# rv_pwr_es_ctrl.net
KiCad netlist of a schematic drawn in Altium Designer
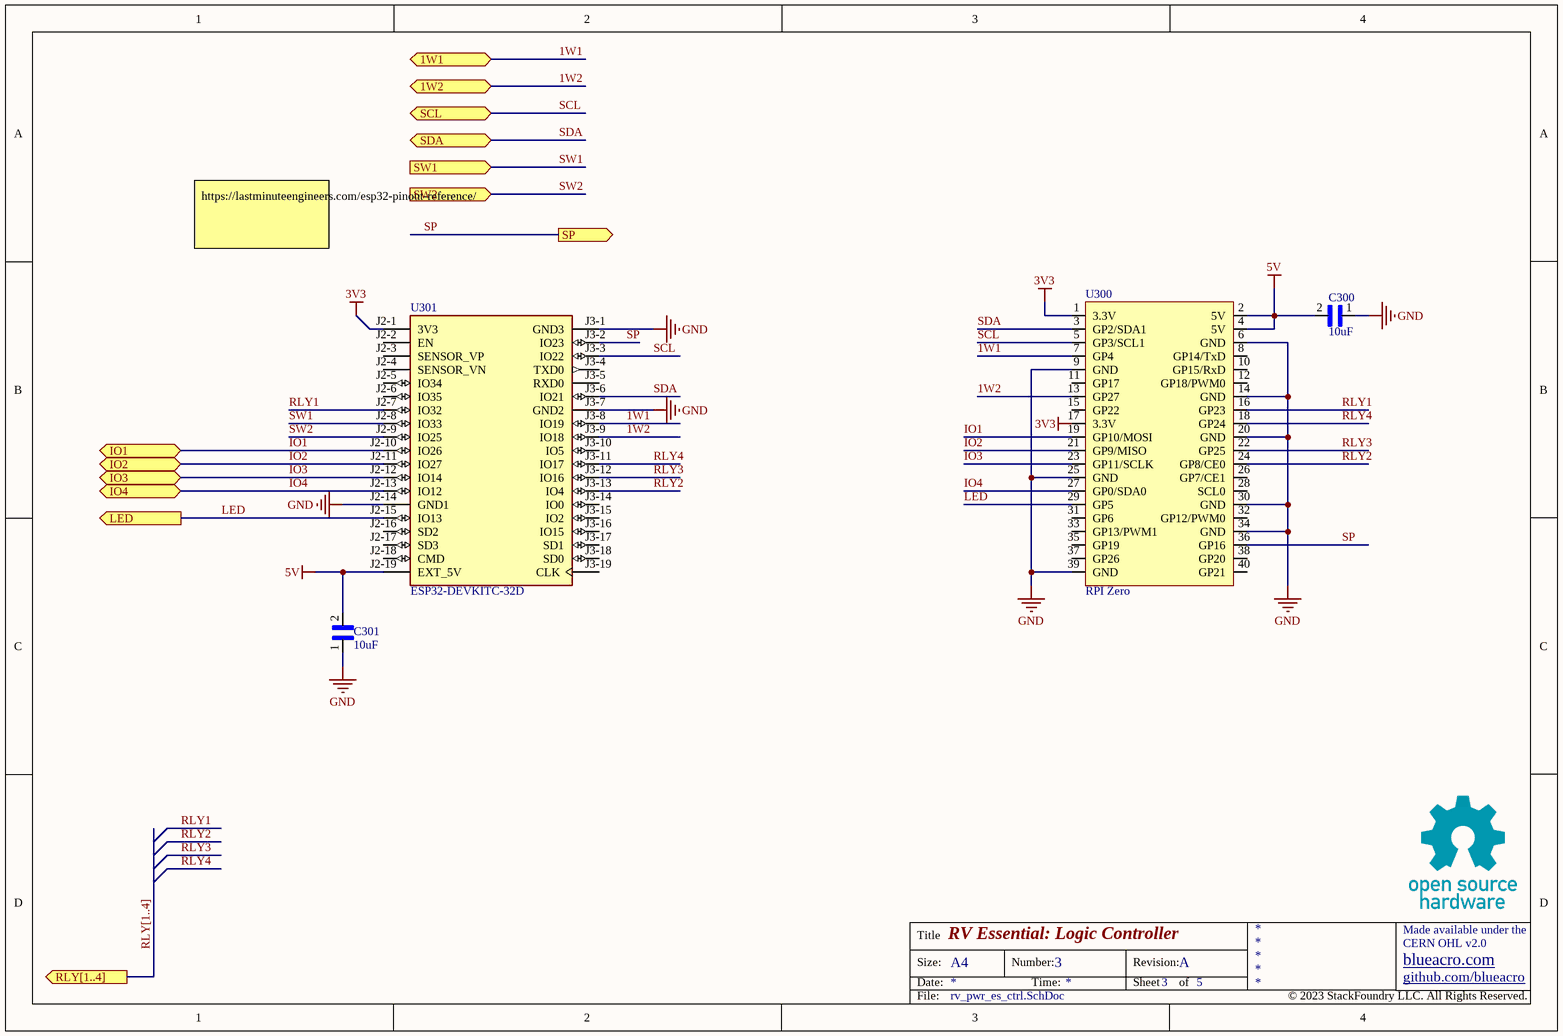
[diagram p0: rv_pwr_es_ctrl.SchDoc]

(export (version "E")
  (design (tool "Eeschema 10.0.6"))
  (components
    (comp (ref "C300")
      (value "10uF")
      (footprint "CAPRB250W50L550T350H600")
      (description "FG Series 10 uF 25 V ±10% Tolerance X7R Radial Multilayer Ceramic Capacitor")
      (fields (field (name "MF") "TDK") (field (name "DIGI-KEY_PART_NUMBER") "445-173156-1-ND"))
      (libsource (lib "") (part "FG16X7R1E106KRT06_1"))
    )
    (comp (ref "C301")
      (value "10uF")
      (footprint "CAPRB250W50L550T350H600")
      (description "FG Series 10 uF 25 V ±10% Tolerance X7R Radial Multilayer Ceramic Capacitor")
      (fields (field (name "MF") "TDK") (field (name "DIGI-KEY_PART_NUMBER") "445-173156-1-ND"))
      (libsource (lib "StackFoundry LLC") (part "FG16X7R1E106KRT06"))
    )
    (comp (ref "U300")
      (value "RPI Zero")
      (footprint "RPI_ZERO_W")
      (libsource (lib "StackFoundry LLC") (part "RPI Zero"))
    )
    (comp (ref "U301")
      (value "ESP32-DEVKITC-32D")
      (footprint "MODULE_ESP32-DEVKITC-32D")
      (description "WiFi Development Tools (802.11) ESP32 General Development Kit, ESP32-WROOM-32D on the board")
      (fields (field (name "MF") "Espressif Systems"))
      (libsource (lib "StackFoundry LLC") (part "ESP32-DEVKITC-32D"))
    )
  )
  (nets
    (net (code "1") (name "/1W1") (class "Default")
      (node (ref "U300") (pin "7") (pinfunction "GP4_7") (pintype "passive"))
      (node (ref "U301") (pin "J3-8") (pinfunction "IO19_J3-8") (pintype "bidirectional"))
    )
    (net (code "2") (name "/1W2") (class "Default")
      (node (ref "U300") (pin "13") (pinfunction "GP27_13") (pintype "passive"))
      (node (ref "U301") (pin "J3-9") (pinfunction "IO18_J3-9") (pintype "bidirectional"))
    )
    (net (code "3") (name "/IO1") (class "Default")
      (node (ref "U300") (pin "19") (pinfunction "GP10/MOSI_19") (pintype "passive"))
      (node (ref "U301") (pin "J2-10") (pinfunction "IO26_J2-10") (pintype "bidirectional"))
    )
    (net (code "4") (name "/IO2") (class "Default")
      (node (ref "U300") (pin "21") (pinfunction "GP9/MISO_21") (pintype "passive"))
      (node (ref "U301") (pin "J2-11") (pinfunction "IO27_J2-11") (pintype "bidirectional"))
    )
    (net (code "5") (name "/IO3") (class "Default")
      (node (ref "U300") (pin "23") (pinfunction "GP11/SCLK_23") (pintype "passive"))
      (node (ref "U301") (pin "J2-12") (pinfunction "IO14_J2-12") (pintype "bidirectional"))
    )
    (net (code "6") (name "/IO4") (class "Default")
      (node (ref "U300") (pin "27") (pinfunction "GP0/SDA0_27") (pintype "passive"))
      (node (ref "U301") (pin "J2-13") (pinfunction "IO12_J2-13") (pintype "bidirectional"))
    )
    (net (code "7") (name "/LED") (class "Default")
      (node (ref "U300") (pin "29") (pinfunction "GP5_29") (pintype "passive"))
      (node (ref "U301") (pin "J2-15") (pinfunction "IO13_J2-15") (pintype "bidirectional"))
    )
    (net (code "8") (name "/RLY1") (class "Default")
      (node (ref "U300") (pin "16") (pinfunction "GP23_16") (pintype "passive"))
      (node (ref "U301") (pin "J2-7") (pinfunction "IO32_J2-7") (pintype "bidirectional"))
    )
    (net (code "9") (name "/RLY2") (class "Default")
      (node (ref "U300") (pin "24") (pinfunction "GP8/CE0_24") (pintype "passive"))
      (node (ref "U301") (pin "J3-13") (pinfunction "IO4_J3-13") (pintype "bidirectional"))
    )
    (net (code "10") (name "/RLY3") (class "Default")
      (node (ref "U300") (pin "22") (pinfunction "GP25_22") (pintype "passive"))
      (node (ref "U301") (pin "J3-12") (pinfunction "IO16_J3-12") (pintype "bidirectional"))
    )
    (net (code "11") (name "/RLY4") (class "Default")
      (node (ref "U300") (pin "18") (pinfunction "GP24_18") (pintype "passive"))
      (node (ref "U301") (pin "J3-11") (pinfunction "IO17_J3-11") (pintype "bidirectional"))
    )
    (net (code "13") (name "/SCL") (class "Default")
      (node (ref "U300") (pin "5") (pinfunction "GP3/SCL1_5") (pintype "passive"))
      (node (ref "U301") (pin "J3-3") (pinfunction "IO22_J3-3") (pintype "bidirectional"))
    )
    (net (code "14") (name "/SDA") (class "Default")
      (node (ref "U300") (pin "3") (pinfunction "GP2/SDA1_3") (pintype "passive"))
      (node (ref "U301") (pin "J3-6") (pinfunction "IO21_J3-6") (pintype "bidirectional"))
    )
    (net (code "15") (name "/SP") (class "Default")
      (node (ref "U300") (pin "36") (pinfunction "GP16_36") (pintype "passive"))
      (node (ref "U301") (pin "J3-2") (pinfunction "IO23_J3-2") (pintype "bidirectional"))
    )
    (net (code "16") (name "/SW1") (class "Default")
      (node (ref "U301") (pin "J2-8") (pinfunction "IO33_J2-8") (pintype "bidirectional"))
    )
    (net (code "17") (name "/SW2") (class "Default")
      (node (ref "U301") (pin "J2-9") (pinfunction "IO25_J2-9") (pintype "bidirectional"))
    )
    (net (code "18") (name "3V3") (class "Default")
      (node (ref "U300") (pin "1") (pinfunction "3.3V_1") (pintype "passive"))
      (node (ref "U300") (pin "17") (pinfunction "3.3V_17") (pintype "passive"))
      (node (ref "U301") (pin "J2-1") (pinfunction "3V3_J2-1") (pintype "power_in"))
    )
    (net (code "19") (name "5V") (class "Default")
      (node (ref "C300") (pin "2") (pinfunction "2_2") (pintype "passive"))
      (node (ref "C301") (pin "2") (pinfunction "2_2") (pintype "passive"))
      (node (ref "U300") (pin "2") (pinfunction "5V_2") (pintype "passive"))
      (node (ref "U300") (pin "4") (pinfunction "5V_4") (pintype "passive"))
      (node (ref "U301") (pin "J2-19") (pinfunction "EXT_5V_J2-19") (pintype "power_in"))
    )
    (net (code "20") (name "GND") (class "Default")
      (node (ref "C300") (pin "1") (pinfunction "1_1") (pintype "passive"))
      (node (ref "C301") (pin "1") (pinfunction "1_1") (pintype "passive"))
      (node (ref "U300") (pin "14") (pinfunction "GND_14") (pintype "passive"))
      (node (ref "U300") (pin "20") (pinfunction "GND_20") (pintype "passive"))
      (node (ref "U300") (pin "25") (pinfunction "GND_25") (pintype "passive"))
      (node (ref "U300") (pin "30") (pinfunction "GND_30") (pintype "passive"))
      (node (ref "U300") (pin "34") (pinfunction "GND_34") (pintype "passive"))
      (node (ref "U300") (pin "39") (pinfunction "GND_39") (pintype "passive"))
      (node (ref "U300") (pin "6") (pinfunction "GND_6") (pintype "passive"))
      (node (ref "U300") (pin "9") (pinfunction "GND_9") (pintype "passive"))
      (node (ref "U301") (pin "J2-14") (pinfunction "GND1_J2-14") (pintype "power_in"))
      (node (ref "U301") (pin "J3-1") (pinfunction "GND3_J3-1") (pintype "power_in"))
      (node (ref "U301") (pin "J3-7") (pinfunction "GND2_J3-7") (pintype "power_in"))
    )
    (net (code "21") (name "unconnected-(U300-GP6-Pad31)") (class "Default")
      (node (ref "U300") (pin "31") (pinfunction "GP6_31") (pintype "passive"))
    )
    (net (code "22") (name "unconnected-(U300-GP7{slash}CE1-Pad26)") (class "Default")
      (node (ref "U300") (pin "26") (pinfunction "GP7/CE1_26") (pintype "passive"))
    )
    (net (code "23") (name "unconnected-(U300-GP12{slash}PWM0-Pad32)") (class "Default")
      (node (ref "U300") (pin "32") (pinfunction "GP12/PWM0_32") (pintype "passive"))
    )
    (net (code "24") (name "unconnected-(U300-GP13{slash}PWM1-Pad33)") (class "Default")
      (node (ref "U300") (pin "33") (pinfunction "GP13/PWM1_33") (pintype "passive"))
    )
    (net (code "25") (name "unconnected-(U300-GP14{slash}TxD-Pad8)") (class "Default")
      (node (ref "U300") (pin "8") (pinfunction "GP14/TxD_8") (pintype "passive"))
    )
    (net (code "26") (name "unconnected-(U300-GP15{slash}RxD-Pad10)") (class "Default")
      (node (ref "U300") (pin "10") (pinfunction "GP15/RxD_10") (pintype "passive"))
    )
    (net (code "27") (name "unconnected-(U300-GP17-Pad11)") (class "Default")
      (node (ref "U300") (pin "11") (pinfunction "GP17_11") (pintype "passive"))
    )
    (net (code "28") (name "unconnected-(U300-GP18{slash}PWM0-Pad12)") (class "Default")
      (node (ref "U300") (pin "12") (pinfunction "GP18/PWM0_12") (pintype "passive"))
    )
    (net (code "29") (name "unconnected-(U300-GP19-Pad35)") (class "Default")
      (node (ref "U300") (pin "35") (pinfunction "GP19_35") (pintype "passive"))
    )
    (net (code "30") (name "unconnected-(U300-GP20-Pad38)") (class "Default")
      (node (ref "U300") (pin "38") (pinfunction "GP20_38") (pintype "passive"))
    )
    (net (code "31") (name "unconnected-(U300-GP21-Pad40)") (class "Default")
      (node (ref "U300") (pin "40") (pinfunction "GP21_40") (pintype "passive"))
    )
    (net (code "32") (name "unconnected-(U300-GP22-Pad15)") (class "Default")
      (node (ref "U300") (pin "15") (pinfunction "GP22_15") (pintype "passive"))
    )
    (net (code "33") (name "unconnected-(U300-GP26-Pad37)") (class "Default")
      (node (ref "U300") (pin "37") (pinfunction "GP26_37") (pintype "passive"))
    )
    (net (code "34") (name "unconnected-(U300-SCL0-Pad28)") (class "Default")
      (node (ref "U300") (pin "28") (pinfunction "SCL0_28") (pintype "passive"))
    )
    (net (code "35") (name "unconnected-(U301-CLK-PadJ3-19)") (class "Default")
      (node (ref "U301") (pin "J3-19") (pinfunction "CLK_J3-19") (pintype "passive"))
    )
    (net (code "36") (name "unconnected-(U301-CMD-PadJ2-18)") (class "Default")
      (node (ref "U301") (pin "J2-18") (pinfunction "CMD_J2-18") (pintype "bidirectional"))
    )
    (net (code "37") (name "unconnected-(U301-EN-PadJ2-2)") (class "Default")
      (node (ref "U301") (pin "J2-2") (pinfunction "EN_J2-2") (pintype "passive"))
    )
    (net (code "38") (name "unconnected-(U301-IO0-PadJ3-14)") (class "Default")
      (node (ref "U301") (pin "J3-14") (pinfunction "IO0_J3-14") (pintype "bidirectional"))
    )
    (net (code "39") (name "unconnected-(U301-IO2-PadJ3-15)") (class "Default")
      (node (ref "U301") (pin "J3-15") (pinfunction "IO2_J3-15") (pintype "bidirectional"))
    )
    (net (code "40") (name "unconnected-(U301-IO5-PadJ3-10)") (class "Default")
      (node (ref "U301") (pin "J3-10") (pinfunction "IO5_J3-10") (pintype "bidirectional"))
    )
    (net (code "41") (name "unconnected-(U301-IO15-PadJ3-16)") (class "Default")
      (node (ref "U301") (pin "J3-16") (pinfunction "IO15_J3-16") (pintype "bidirectional"))
    )
    (net (code "42") (name "unconnected-(U301-IO34-PadJ2-5)") (class "Default")
      (node (ref "U301") (pin "J2-5") (pinfunction "IO34_J2-5") (pintype "bidirectional"))
    )
    (net (code "43") (name "unconnected-(U301-IO35-PadJ2-6)") (class "Default")
      (node (ref "U301") (pin "J2-6") (pinfunction "IO35_J2-6") (pintype "bidirectional"))
    )
    (net (code "44") (name "unconnected-(U301-RXD0-PadJ3-5)") (class "Default")
      (node (ref "U301") (pin "J3-5") (pinfunction "RXD0_J3-5") (pintype "passive"))
    )
    (net (code "45") (name "unconnected-(U301-SD0-PadJ3-18)") (class "Default")
      (node (ref "U301") (pin "J3-18") (pinfunction "SD0_J3-18") (pintype "bidirectional"))
    )
    (net (code "46") (name "unconnected-(U301-SD1-PadJ3-17)") (class "Default")
      (node (ref "U301") (pin "J3-17") (pinfunction "SD1_J3-17") (pintype "bidirectional"))
    )
    (net (code "47") (name "unconnected-(U301-SD2-PadJ2-16)") (class "Default")
      (node (ref "U301") (pin "J2-16") (pinfunction "SD2_J2-16") (pintype "bidirectional"))
    )
    (net (code "48") (name "unconnected-(U301-SD3-PadJ2-17)") (class "Default")
      (node (ref "U301") (pin "J2-17") (pinfunction "SD3_J2-17") (pintype "bidirectional"))
    )
    (net (code "49") (name "unconnected-(U301-SENSOR_VN-PadJ2-4)") (class "Default")
      (node (ref "U301") (pin "J2-4") (pinfunction "SENSOR_VN_J2-4") (pintype "passive"))
    )
    (net (code "50") (name "unconnected-(U301-SENSOR_VP-PadJ2-3)") (class "Default")
      (node (ref "U301") (pin "J2-3") (pinfunction "SENSOR_VP_J2-3") (pintype "passive"))
    )
    (net (code "51") (name "unconnected-(U301-TXD0-PadJ3-4)") (class "Default")
      (node (ref "U301") (pin "J3-4") (pinfunction "TXD0_J3-4") (pintype "output"))
    )
  )
)
